# 13-IO.net
KiCad netlist of a schematic drawn in Altium Designer
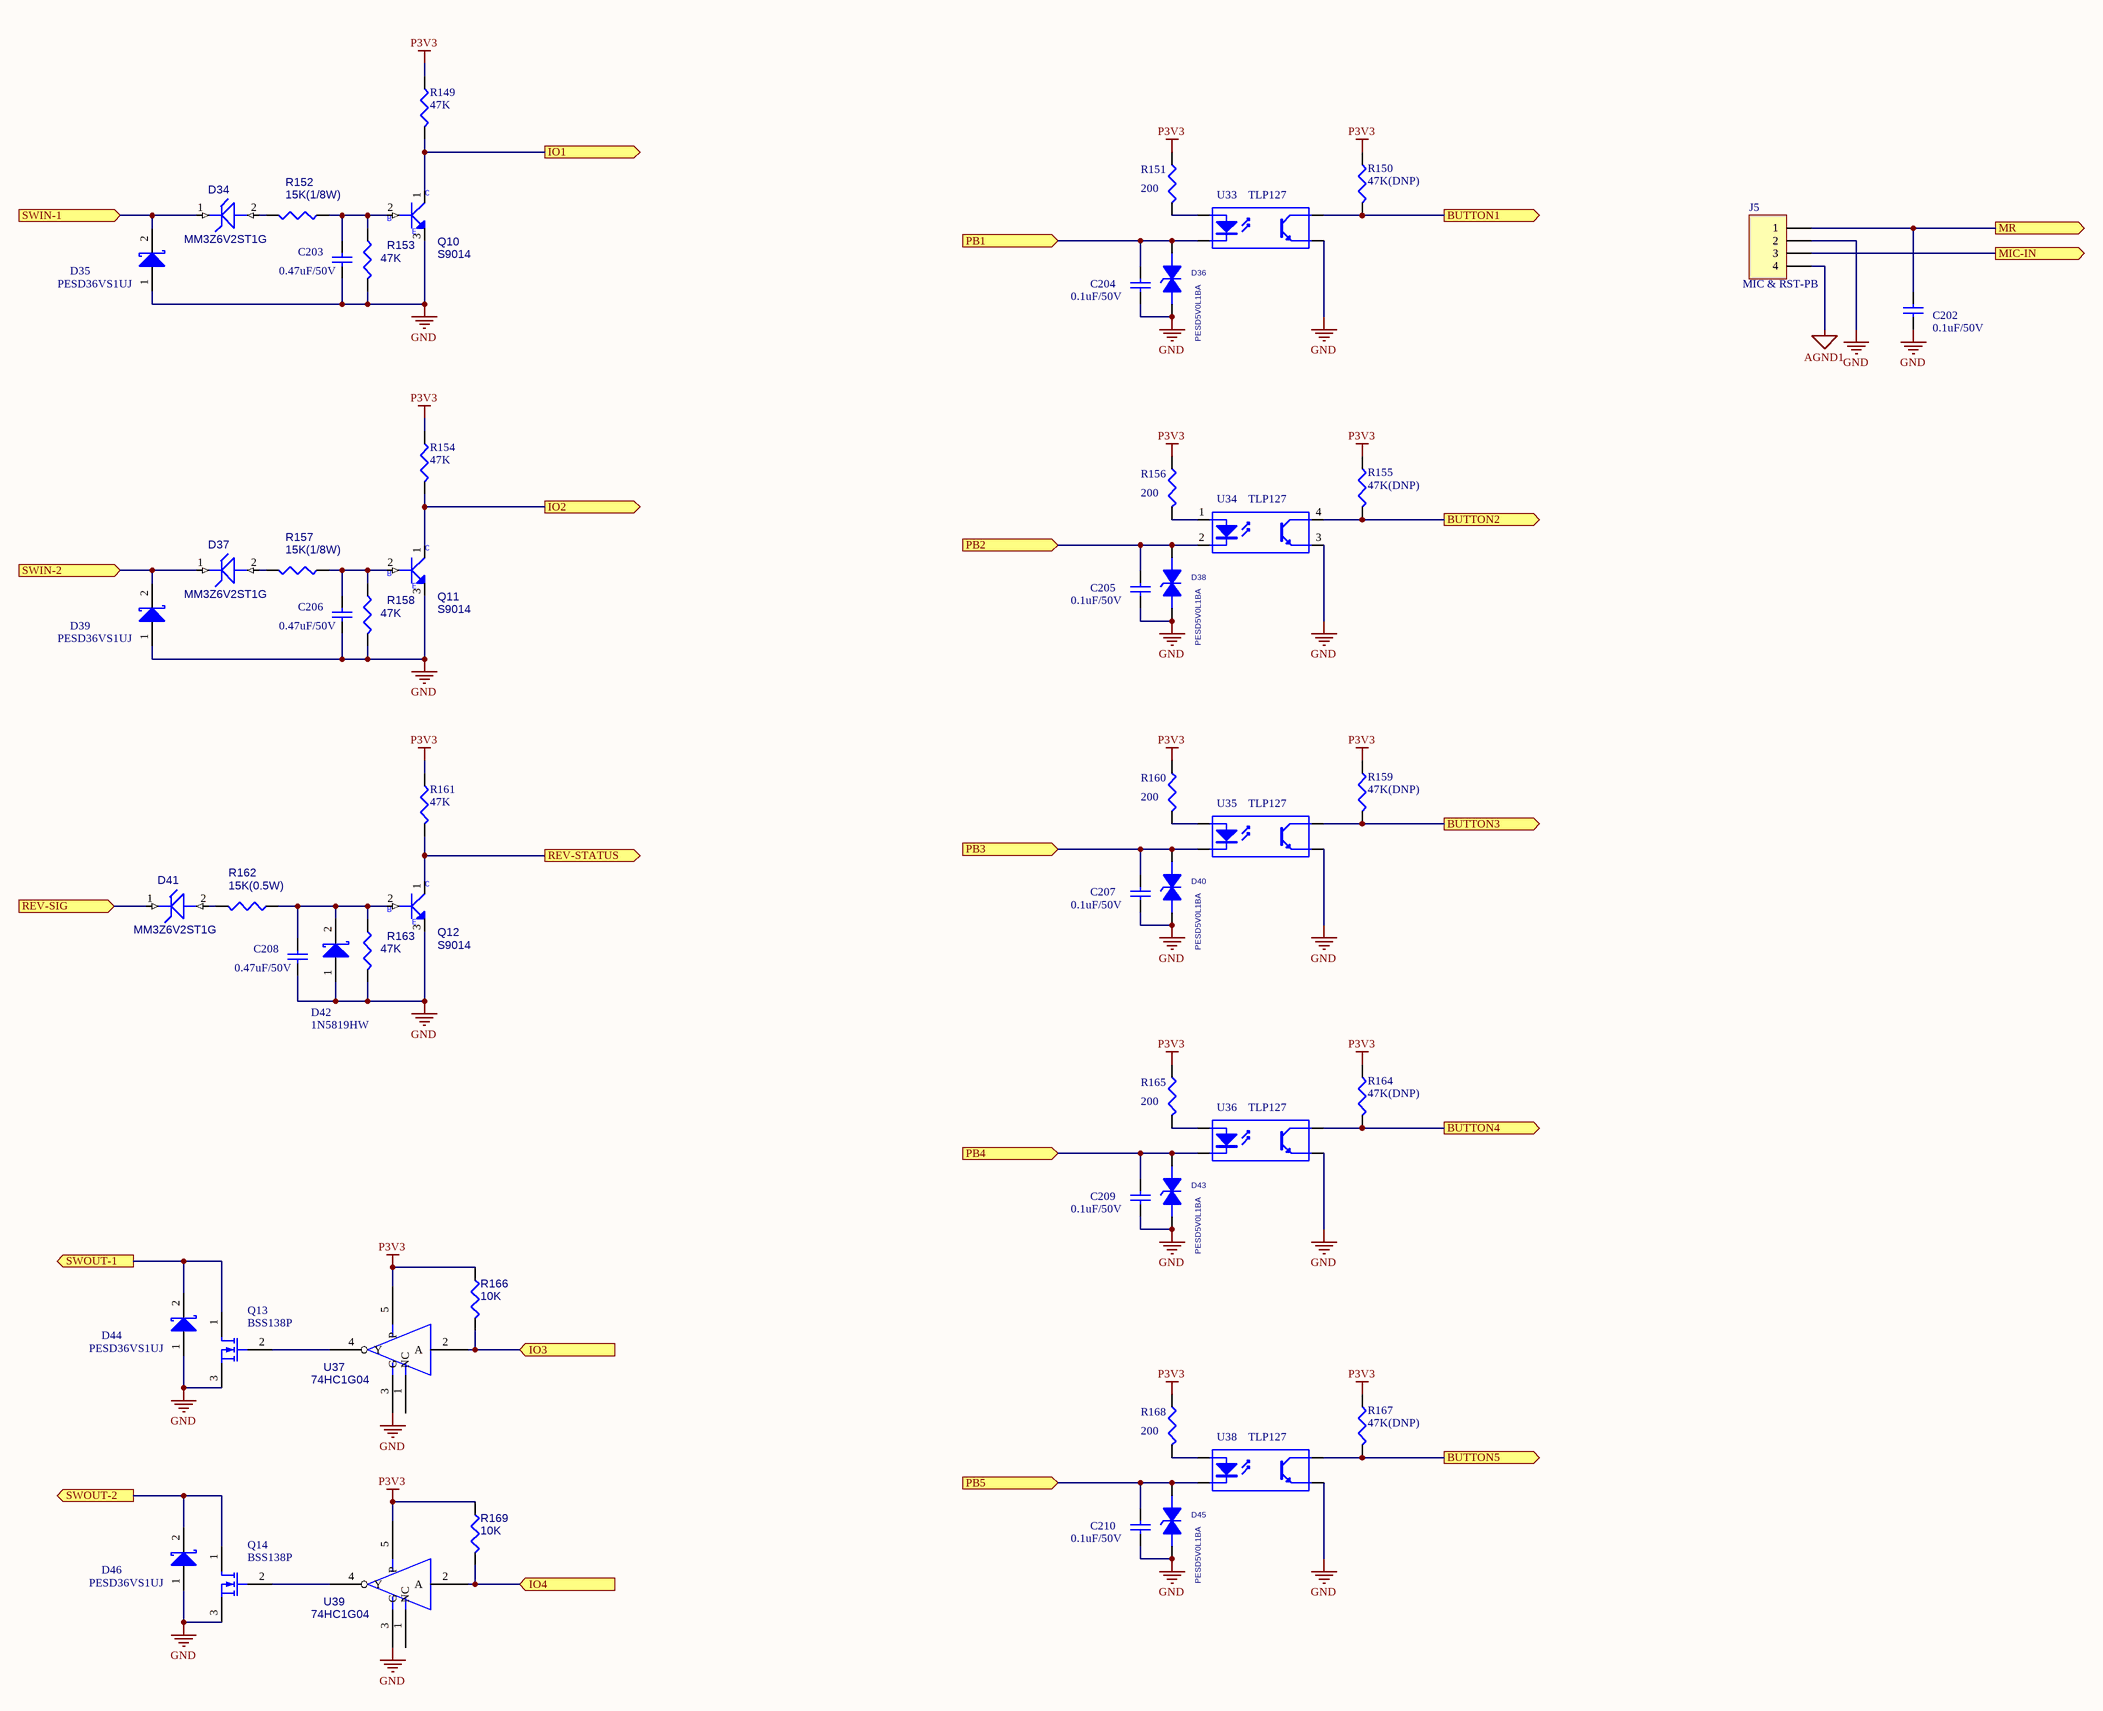
[diagram p0: 13-IO.SchDoc]

(export (version "E")
  (design (tool "Eeschema 10.0.6"))
  (components
    (comp (ref "C202")
      (value "0.1uF/50V")
      (footprint "0402")
      (description "Capacitor")
      (fields (field (name "PUBLISHER") "Altium Limited"))
      (libsource (lib "Miscellaneous Devices") (part "Cap"))
    )
    (comp (ref "C203")
      (value "0.47uF/50V")
      (footprint "0603")
      (description "Capacitor")
      (fields (field (name "PUBLISHER") "Altium Limited"))
      (libsource (lib "Miscellaneous Devices") (part "Cap"))
    )
    (comp (ref "C204")
      (value "0.1uF/50V")
      (footprint "0402")
      (description "Capacitor")
      (fields (field (name "PUBLISHER") "Altium Limited"))
      (libsource (lib "Miscellaneous Devices") (part "Cap"))
    )
    (comp (ref "C205")
      (value "0.1uF/50V")
      (footprint "0402")
      (description "Capacitor")
      (fields (field (name "PUBLISHER") "Altium Limited"))
      (libsource (lib "Miscellaneous Devices") (part "Cap"))
    )
    (comp (ref "C206")
      (value "0.47uF/50V")
      (footprint "0603")
      (description "Capacitor")
      (fields (field (name "PUBLISHER") "Altium Limited"))
      (libsource (lib "Miscellaneous Devices") (part "Cap"))
    )
    (comp (ref "C207")
      (value "0.1uF/50V")
      (footprint "0402")
      (description "Capacitor")
      (fields (field (name "PUBLISHER") "Altium Limited"))
      (libsource (lib "Miscellaneous Devices") (part "Cap"))
    )
    (comp (ref "C208")
      (value "0.47uF/50V")
      (footprint "0603")
      (description "Capacitor")
      (fields (field (name "PUBLISHER") "Altium Limited"))
      (libsource (lib "Miscellaneous Devices") (part "Cap"))
    )
    (comp (ref "C209")
      (value "0.1uF/50V")
      (footprint "0402")
      (description "Capacitor")
      (fields (field (name "PUBLISHER") "Altium Limited"))
      (libsource (lib "Miscellaneous Devices") (part "Cap"))
    )
    (comp (ref "C210")
      (value "0.1uF/50V")
      (footprint "0402")
      (description "Capacitor")
      (fields (field (name "PUBLISHER") "Altium Limited"))
      (libsource (lib "Miscellaneous Devices") (part "Cap"))
    )
    (comp (ref "D34")
      (value "MM3Z6V2ST1G")
      (footprint "SOD323F")
      (libsource (lib "*") (part "MMGZ5231BPTLL34"))
    )
    (comp (ref "D35")
      (value "PESD36VS1UJ")
      (footprint "SOD323")
      (description "Schottky Rectifier")
      (libsource (lib "Miscellaneous Devices") (part "Diode 11DQ03"))
    )
    (comp (ref "D36") (value "PESD5V0L1BA") (libsource (lib "*") (part "PESD")))
    (comp (ref "D37")
      (value "MM3Z6V2ST1G")
      (footprint "SOD323F")
      (libsource (lib "*") (part "MMGZ5231BPTLL34"))
    )
    (comp (ref "D38") (value "PESD5V0L1BA") (libsource (lib "*") (part "PESD")))
    (comp (ref "D39")
      (value "PESD36VS1UJ")
      (footprint "SOD323")
      (description "Schottky Rectifier")
      (libsource (lib "Miscellaneous Devices") (part "Diode 11DQ03"))
    )
    (comp (ref "D40") (value "PESD5V0L1BA") (libsource (lib "*") (part "PESD")))
    (comp (ref "D41")
      (value "MM3Z6V2ST1G")
      (footprint "SOD323F")
      (libsource (lib "*") (part "MMGZ5231BPTLL34"))
    )
    (comp (ref "D42")
      (value "1N5819HW")
      (footprint "1N5819")
      (description "Schottky Rectifier")
      (libsource (lib "Miscellaneous Devices") (part "Diode 11DQ03"))
    )
    (comp (ref "D43") (value "PESD5V0L1BA") (libsource (lib "*") (part "PESD")))
    (comp (ref "D44")
      (value "PESD36VS1UJ")
      (footprint "SOD323")
      (description "Schottky Rectifier")
      (libsource (lib "Miscellaneous Devices") (part "Diode 11DQ03"))
    )
    (comp (ref "D45") (value "PESD5V0L1BA") (libsource (lib "*") (part "PESD")))
    (comp (ref "D46")
      (value "PESD36VS1UJ")
      (footprint "SOD323")
      (description "Schottky Rectifier")
      (libsource (lib "Miscellaneous Devices") (part "Diode 11DQ03"))
    )
    (comp (ref "J5")
      (value "MIC & RST-PB")
      (footprint "FPC1.0-DR-SMD-4P-F2.0")
      (description "Header, 4-Pin")
      (fields (field (name "PUBLISHER") "Altium Limited"))
      (libsource (lib "Miscellaneous Connectors") (part "Header 4"))
    )
    (comp (ref "Q10")
      (value "S9014")
      (footprint "NPN")
      (fields (field (name "PART NUMBER") "SB039040000"))
      (libsource (lib "*") (part "MMBT3904_NL_SOT23-3"))
    )
    (comp (ref "Q11")
      (value "S9014")
      (footprint "NPN")
      (fields (field (name "PART NUMBER") "SB039040000"))
      (libsource (lib "*") (part "MMBT3904_NL_SOT23-3"))
    )
    (comp (ref "Q12")
      (value "S9014")
      (footprint "NPN")
      (fields (field (name "PART NUMBER") "SB039040000"))
      (libsource (lib "*") (part "MMBT3904_NL_SOT23-3"))
    )
    (comp (ref "Q13")
      (value "BSS138P")
      (footprint "NPN")
      (description "N-Channel MOSFET")
      (fields (field (name "PUBLISHER") "Altium Limited"))
      (libsource (lib "Miscellaneous Devices") (part "MOSFET-N"))
    )
    (comp (ref "Q14")
      (value "BSS138P")
      (footprint "NPN")
      (description "N-Channel MOSFET")
      (fields (field (name "PUBLISHER") "Altium Limited"))
      (libsource (lib "Miscellaneous Devices") (part "MOSFET-N"))
    )
    (comp (ref "R149") (value "47K") (footprint "0402") (libsource (lib "*") (part "CR16-1003FM")))
    (comp (ref "R150") (value "47K(DNP)") (footprint "0402") (libsource (lib "*") (part "CR16-1003FM")))
    (comp (ref "R151") (value "200") (footprint "0402") (libsource (lib "*") (part "CR16-1003FM")))
    (comp (ref "R152") (value "15K(1/8W)") (libsource (lib "*") (part "R")))
    (comp (ref "R153") (value "47K") (libsource (lib "*") (part "R")))
    (comp (ref "R154") (value "47K") (footprint "0402") (libsource (lib "*") (part "CR16-1003FM")))
    (comp (ref "R155") (value "47K(DNP)") (footprint "0402") (libsource (lib "*") (part "CR16-1003FM")))
    (comp (ref "R156") (value "200") (footprint "0402") (libsource (lib "*") (part "CR16-1003FM")))
    (comp (ref "R157") (value "15K(1/8W)") (libsource (lib "*") (part "R")))
    (comp (ref "R158") (value "47K") (libsource (lib "*") (part "R")))
    (comp (ref "R159") (value "47K(DNP)") (footprint "0402") (libsource (lib "*") (part "CR16-1003FM")))
    (comp (ref "R160") (value "200") (footprint "0402") (libsource (lib "*") (part "CR16-1003FM")))
    (comp (ref "R161") (value "47K") (footprint "0402") (libsource (lib "*") (part "CR16-1003FM")))
    (comp (ref "R162") (value "15K(0.5W)") (libsource (lib "*") (part "R")))
    (comp (ref "R163") (value "47K") (libsource (lib "*") (part "R")))
    (comp (ref "R164") (value "47K(DNP)") (footprint "0402") (libsource (lib "*") (part "CR16-1003FM")))
    (comp (ref "R165") (value "200") (footprint "0402") (libsource (lib "*") (part "CR16-1003FM")))
    (comp (ref "R166") (value "10K") (libsource (lib "*") (part "R")))
    (comp (ref "R167") (value "47K(DNP)") (footprint "0402") (libsource (lib "*") (part "CR16-1003FM")))
    (comp (ref "R168") (value "200") (footprint "0402") (libsource (lib "*") (part "CR16-1003FM")))
    (comp (ref "R169") (value "10K") (libsource (lib "*") (part "R")))
    (comp (ref "U33")
      (value "TLP127")
      (footprint "TLP127")
      (description "4-Pin Phototransistor Optocoupler")
      (fields (field (name "PUBLISHER") "Altium Limited"))
      (libsource (lib "Miscellaneous Devices") (part "Optoisolator1"))
    )
    (comp (ref "U34")
      (value "TLP127")
      (footprint "TLP127")
      (description "4-Pin Phototransistor Optocoupler")
      (fields (field (name "PUBLISHER") "Altium Limited"))
      (libsource (lib "") (part "Optoisolator1_1"))
    )
    (comp (ref "U35")
      (value "TLP127")
      (footprint "TLP127")
      (description "4-Pin Phototransistor Optocoupler")
      (fields (field (name "PUBLISHER") "Altium Limited"))
      (libsource (lib "Miscellaneous Devices") (part "Optoisolator1"))
    )
    (comp (ref "U36")
      (value "TLP127")
      (footprint "TLP127")
      (description "4-Pin Phototransistor Optocoupler")
      (fields (field (name "PUBLISHER") "Altium Limited"))
      (libsource (lib "Miscellaneous Devices") (part "Optoisolator1"))
    )
    (comp (ref "U37") (value "74HC1G04") (libsource (lib "*") (part "74LVC1G04GW_SOT353-5")))
    (comp (ref "U38")
      (value "TLP127")
      (footprint "TLP127")
      (description "4-Pin Phototransistor Optocoupler")
      (fields (field (name "PUBLISHER") "Altium Limited"))
      (libsource (lib "Miscellaneous Devices") (part "Optoisolator1"))
    )
    (comp (ref "U39") (value "74HC1G04") (libsource (lib "*") (part "74LVC1G04GW_SOT353-5")))
  )
  (nets
    (net (code "1") (name "/BUTTON1") (class "Default")
      (node (ref "R150") (pin "2") (pinfunction "2_2") (pintype "passive"))
      (node (ref "U33") (pin "4") (pinfunction "C_4") (pintype "passive"))
    )
    (net (code "2") (name "/BUTTON2") (class "Default")
      (node (ref "R155") (pin "2") (pinfunction "2_2") (pintype "passive"))
      (node (ref "U34") (pin "4") (pinfunction "C_4") (pintype "passive"))
    )
    (net (code "3") (name "/BUTTON3") (class "Default")
      (node (ref "R159") (pin "2") (pinfunction "2_2") (pintype "passive"))
      (node (ref "U35") (pin "4") (pinfunction "C_4") (pintype "passive"))
    )
    (net (code "4") (name "/BUTTON4") (class "Default")
      (node (ref "R164") (pin "2") (pinfunction "2_2") (pintype "passive"))
      (node (ref "U36") (pin "4") (pinfunction "C_4") (pintype "passive"))
    )
    (net (code "5") (name "/BUTTON5") (class "Default")
      (node (ref "R167") (pin "2") (pinfunction "2_2") (pintype "passive"))
      (node (ref "U38") (pin "4") (pinfunction "C_4") (pintype "passive"))
    )
    (net (code "6") (name "/IO1") (class "Default")
      (node (ref "Q10") (pin "1") (pinfunction "COLLECTOR_1") (pintype "passive"))
      (node (ref "R149") (pin "2") (pinfunction "2_2") (pintype "passive"))
    )
    (net (code "7") (name "/IO2") (class "Default")
      (node (ref "Q11") (pin "1") (pinfunction "COLLECTOR_1") (pintype "passive"))
      (node (ref "R154") (pin "2") (pinfunction "2_2") (pintype "passive"))
    )
    (net (code "8") (name "/IO3") (class "Default")
      (node (ref "R166") (pin "2") (pinfunction "2_2") (pintype "passive"))
      (node (ref "U37") (pin "2") (pinfunction "A_2") (pintype "passive"))
    )
    (net (code "9") (name "/IO4") (class "Default")
      (node (ref "R169") (pin "2") (pinfunction "2_2") (pintype "passive"))
      (node (ref "U39") (pin "2") (pinfunction "A_2") (pintype "passive"))
    )
    (net (code "10") (name "/MIC-IN") (class "Default")
      (node (ref "J5") (pin "3") (pinfunction "3_3") (pintype "passive"))
    )
    (net (code "11") (name "/MR") (class "Default")
      (node (ref "C202") (pin "1") (pinfunction "1_1") (pintype "passive"))
      (node (ref "J5") (pin "1") (pinfunction "1_1") (pintype "passive"))
    )
    (net (code "12") (name "/PB1") (class "Default")
      (node (ref "C204") (pin "1") (pinfunction "1_1") (pintype "passive"))
      (node (ref "D36") (pin "2") (pinfunction "2_2") (pintype "passive"))
      (node (ref "U33") (pin "2") (pinfunction "K_2") (pintype "passive"))
    )
    (net (code "13") (name "/PB2") (class "Default")
      (node (ref "C205") (pin "1") (pinfunction "1_1") (pintype "passive"))
      (node (ref "D38") (pin "2") (pinfunction "2_2") (pintype "passive"))
      (node (ref "U34") (pin "2") (pinfunction "K_2") (pintype "passive"))
    )
    (net (code "14") (name "/PB3") (class "Default")
      (node (ref "C207") (pin "1") (pinfunction "1_1") (pintype "passive"))
      (node (ref "D40") (pin "2") (pinfunction "2_2") (pintype "passive"))
      (node (ref "U35") (pin "2") (pinfunction "K_2") (pintype "passive"))
    )
    (net (code "15") (name "/PB4") (class "Default")
      (node (ref "C209") (pin "1") (pinfunction "1_1") (pintype "passive"))
      (node (ref "D43") (pin "2") (pinfunction "2_2") (pintype "passive"))
      (node (ref "U36") (pin "2") (pinfunction "K_2") (pintype "passive"))
    )
    (net (code "16") (name "/PB5") (class "Default")
      (node (ref "C210") (pin "1") (pinfunction "1_1") (pintype "passive"))
      (node (ref "D45") (pin "2") (pinfunction "2_2") (pintype "passive"))
      (node (ref "U38") (pin "2") (pinfunction "K_2") (pintype "passive"))
    )
    (net (code "17") (name "/REV-SIG") (class "Default")
      (node (ref "D41") (pin "1") (pinfunction "1_1") (pintype "input"))
    )
    (net (code "18") (name "/REV-STATUS") (class "Default")
      (node (ref "Q12") (pin "1") (pinfunction "COLLECTOR_1") (pintype "passive"))
      (node (ref "R161") (pin "2") (pinfunction "2_2") (pintype "passive"))
    )
    (net (code "19") (name "/SWIN-1") (class "Default")
      (node (ref "D34") (pin "1") (pinfunction "1_1") (pintype "input"))
      (node (ref "D35") (pin "2") (pinfunction "K_2") (pintype "passive"))
    )
    (net (code "20") (name "/SWIN-2") (class "Default")
      (node (ref "D37") (pin "1") (pinfunction "1_1") (pintype "input"))
      (node (ref "D39") (pin "2") (pinfunction "K_2") (pintype "passive"))
    )
    (net (code "21") (name "/SWOUT-1") (class "Default")
      (node (ref "D44") (pin "2") (pinfunction "K_2") (pintype "passive"))
      (node (ref "Q13") (pin "1") (pinfunction "D_1") (pintype "passive"))
    )
    (net (code "22") (name "/SWOUT-2") (class "Default")
      (node (ref "D46") (pin "2") (pinfunction "K_2") (pintype "passive"))
      (node (ref "Q14") (pin "1") (pinfunction "D_1") (pintype "passive"))
    )
    (net (code "23") (name "AGND1") (class "Default")
      (node (ref "J5") (pin "4") (pinfunction "4_4") (pintype "passive"))
    )
    (net (code "24") (name "GND") (class "Default")
      (node (ref "C202") (pin "2") (pinfunction "2_2") (pintype "passive"))
      (node (ref "C203") (pin "2") (pinfunction "2_2") (pintype "passive"))
      (node (ref "C204") (pin "2") (pinfunction "2_2") (pintype "passive"))
      (node (ref "C205") (pin "2") (pinfunction "2_2") (pintype "passive"))
      (node (ref "C206") (pin "2") (pinfunction "2_2") (pintype "passive"))
      (node (ref "C207") (pin "2") (pinfunction "2_2") (pintype "passive"))
      (node (ref "C208") (pin "2") (pinfunction "2_2") (pintype "passive"))
      (node (ref "C209") (pin "2") (pinfunction "2_2") (pintype "passive"))
      (node (ref "C210") (pin "2") (pinfunction "2_2") (pintype "passive"))
      (node (ref "D35") (pin "1") (pinfunction "A_1") (pintype "passive"))
      (node (ref "D36") (pin "1") (pinfunction "1_1") (pintype "passive"))
      (node (ref "D38") (pin "1") (pinfunction "1_1") (pintype "passive"))
      (node (ref "D39") (pin "1") (pinfunction "A_1") (pintype "passive"))
      (node (ref "D40") (pin "1") (pinfunction "1_1") (pintype "passive"))
      (node (ref "D42") (pin "1") (pinfunction "A_1") (pintype "passive"))
      (node (ref "D43") (pin "1") (pinfunction "1_1") (pintype "passive"))
      (node (ref "D44") (pin "1") (pinfunction "A_1") (pintype "passive"))
      (node (ref "D45") (pin "1") (pinfunction "1_1") (pintype "passive"))
      (node (ref "D46") (pin "1") (pinfunction "A_1") (pintype "passive"))
      (node (ref "J5") (pin "2") (pinfunction "2_2") (pintype "passive"))
      (node (ref "Q10") (pin "3") (pinfunction "EMITTER_3") (pintype "passive"))
      (node (ref "Q11") (pin "3") (pinfunction "EMITTER_3") (pintype "passive"))
      (node (ref "Q12") (pin "3") (pinfunction "EMITTER_3") (pintype "passive"))
      (node (ref "Q13") (pin "3") (pinfunction "S_3") (pintype "passive"))
      (node (ref "Q14") (pin "3") (pinfunction "S_3") (pintype "passive"))
      (node (ref "R153") (pin "2") (pinfunction "2_2") (pintype "passive"))
      (node (ref "R158") (pin "2") (pinfunction "2_2") (pintype "passive"))
      (node (ref "R163") (pin "2") (pinfunction "2_2") (pintype "passive"))
      (node (ref "U33") (pin "3") (pinfunction "E_3") (pintype "passive"))
      (node (ref "U34") (pin "3") (pinfunction "E_3") (pintype "passive"))
      (node (ref "U35") (pin "3") (pinfunction "E_3") (pintype "passive"))
      (node (ref "U36") (pin "3") (pinfunction "E_3") (pintype "passive"))
      (node (ref "U37") (pin "3") (pinfunction "G_3") (pintype "passive"))
      (node (ref "U38") (pin "3") (pinfunction "E_3") (pintype "passive"))
      (node (ref "U39") (pin "3") (pinfunction "G_3") (pintype "passive"))
    )
    (net (code "25") (name "Net-(D34-Pad2)") (class "Default")
      (node (ref "D34") (pin "2") (pinfunction "2_2") (pintype "input"))
      (node (ref "R152") (pin "2") (pinfunction "2_2") (pintype "passive"))
    )
    (net (code "26") (name "Net-(D37-Pad2)") (class "Default")
      (node (ref "D37") (pin "2") (pinfunction "2_2") (pintype "input"))
      (node (ref "R157") (pin "2") (pinfunction "2_2") (pintype "passive"))
    )
    (net (code "27") (name "Net-(D41-Pad2)") (class "Default")
      (node (ref "D41") (pin "2") (pinfunction "2_2") (pintype "input"))
      (node (ref "R162") (pin "2") (pinfunction "2_2") (pintype "passive"))
    )
    (net (code "28") (name "Net-(D42-K)") (class "Default")
      (node (ref "C208") (pin "1") (pinfunction "1_1") (pintype "passive"))
      (node (ref "D42") (pin "2") (pinfunction "K_2") (pintype "passive"))
      (node (ref "Q12") (pin "2") (pinfunction "BASE_2") (pintype "input"))
      (node (ref "R162") (pin "1") (pinfunction "1_1") (pintype "passive"))
      (node (ref "R163") (pin "1") (pinfunction "1_1") (pintype "passive"))
    )
    (net (code "29") (name "Net-(Q10-BASE)") (class "Default")
      (node (ref "C203") (pin "1") (pinfunction "1_1") (pintype "passive"))
      (node (ref "Q10") (pin "2") (pinfunction "BASE_2") (pintype "input"))
      (node (ref "R152") (pin "1") (pinfunction "1_1") (pintype "passive"))
      (node (ref "R153") (pin "1") (pinfunction "1_1") (pintype "passive"))
    )
    (net (code "30") (name "Net-(Q11-BASE)") (class "Default")
      (node (ref "C206") (pin "1") (pinfunction "1_1") (pintype "passive"))
      (node (ref "Q11") (pin "2") (pinfunction "BASE_2") (pintype "input"))
      (node (ref "R157") (pin "1") (pinfunction "1_1") (pintype "passive"))
      (node (ref "R158") (pin "1") (pinfunction "1_1") (pintype "passive"))
    )
    (net (code "31") (name "Net-(Q13-G)") (class "Default")
      (node (ref "Q13") (pin "2") (pinfunction "G_2") (pintype "passive"))
      (node (ref "U37") (pin "4") (pinfunction "Y_4") (pintype "passive"))
    )
    (net (code "32") (name "Net-(Q14-G)") (class "Default")
      (node (ref "Q14") (pin "2") (pinfunction "G_2") (pintype "passive"))
      (node (ref "U39") (pin "4") (pinfunction "Y_4") (pintype "passive"))
    )
    (net (code "33") (name "Net-(U33-A)") (class "Default")
      (node (ref "R151") (pin "2") (pinfunction "2_2") (pintype "passive"))
      (node (ref "U33") (pin "1") (pinfunction "A_1") (pintype "passive"))
    )
    (net (code "34") (name "Net-(U34-A)") (class "Default")
      (node (ref "R156") (pin "2") (pinfunction "2_2") (pintype "passive"))
      (node (ref "U34") (pin "1") (pinfunction "A_1") (pintype "passive"))
    )
    (net (code "35") (name "Net-(U35-A)") (class "Default")
      (node (ref "R160") (pin "2") (pinfunction "2_2") (pintype "passive"))
      (node (ref "U35") (pin "1") (pinfunction "A_1") (pintype "passive"))
    )
    (net (code "36") (name "Net-(U36-A)") (class "Default")
      (node (ref "R165") (pin "2") (pinfunction "2_2") (pintype "passive"))
      (node (ref "U36") (pin "1") (pinfunction "A_1") (pintype "passive"))
    )
    (net (code "37") (name "Net-(U38-A)") (class "Default")
      (node (ref "R168") (pin "2") (pinfunction "2_2") (pintype "passive"))
      (node (ref "U38") (pin "1") (pinfunction "A_1") (pintype "passive"))
    )
    (net (code "38") (name "P3V3") (class "Default")
      (node (ref "R149") (pin "1") (pinfunction "1_1") (pintype "passive"))
      (node (ref "R150") (pin "1") (pinfunction "1_1") (pintype "passive"))
      (node (ref "R151") (pin "1") (pinfunction "1_1") (pintype "passive"))
      (node (ref "R154") (pin "1") (pinfunction "1_1") (pintype "passive"))
      (node (ref "R155") (pin "1") (pinfunction "1_1") (pintype "passive"))
      (node (ref "R156") (pin "1") (pinfunction "1_1") (pintype "passive"))
      (node (ref "R159") (pin "1") (pinfunction "1_1") (pintype "passive"))
      (node (ref "R160") (pin "1") (pinfunction "1_1") (pintype "passive"))
      (node (ref "R161") (pin "1") (pinfunction "1_1") (pintype "passive"))
      (node (ref "R164") (pin "1") (pinfunction "1_1") (pintype "passive"))
      (node (ref "R165") (pin "1") (pinfunction "1_1") (pintype "passive"))
      (node (ref "R166") (pin "1") (pinfunction "1_1") (pintype "passive"))
      (node (ref "R167") (pin "1") (pinfunction "1_1") (pintype "passive"))
      (node (ref "R168") (pin "1") (pinfunction "1_1") (pintype "passive"))
      (node (ref "R169") (pin "1") (pinfunction "1_1") (pintype "passive"))
      (node (ref "U37") (pin "5") (pinfunction "P_5") (pintype "passive"))
      (node (ref "U39") (pin "5") (pinfunction "P_5") (pintype "passive"))
    )
    (net (code "39") (name "unconnected-(U37-NC-Pad1)") (class "Default")
      (node (ref "U37") (pin "1") (pinfunction "NC_1") (pintype "passive"))
    )
    (net (code "40") (name "unconnected-(U39-NC-Pad1)") (class "Default")
      (node (ref "U39") (pin "1") (pinfunction "NC_1") (pintype "passive"))
    )
  )
)
